# 8051.net
KiCad netlist of a schematic drawn in EAGLE
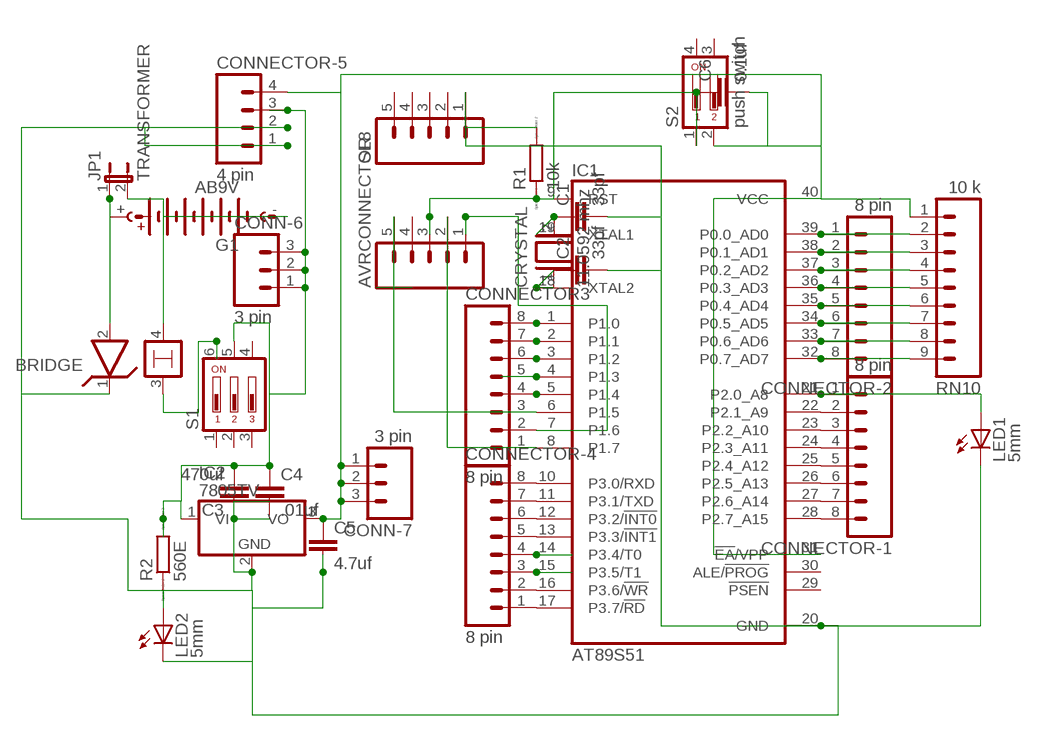
[diagram p0: schematic, sheet 1]

(export (version "E")
  (design (tool "Eeschema 10.0.6"))
  (components
    (comp (ref "AVRCONNECTOR")
      (value "M05")
      (footprint "eagle-import:05P")
      (libsource (lib "eagle-import") (part "M05"))
    )
    (comp (ref "BRIDGE")
      (value "LM399H")
      (footprint "eagle-import:TO39_4")
      (libsource (lib "eagle-import") (part "LM399H"))
    )
    (comp (ref "C1")
      (value "33pf")
      (footprint "eagle-import:C025-024X044")
      (libsource (lib "eagle-import") (part "C-EU025-024X044"))
    )
    (comp (ref "C2")
      (value "33pf")
      (footprint "eagle-import:C025-024X044")
      (libsource (lib "eagle-import") (part "C-EU025-024X044"))
    )
    (comp (ref "C3")
      (value "470uf")
      (footprint "eagle-import:C5B7.2")
      (libsource (lib "eagle-import") (part "C5/7.2"))
    )
    (comp (ref "C4")
      (value ".01uf")
      (footprint "eagle-import:C2.5-3")
      (libsource (lib "eagle-import") (part "C2,5-3"))
    )
    (comp (ref "C5")
      (value "4.7uf")
      (footprint "eagle-import:C2.5-3")
      (libsource (lib "eagle-import") (part "C2,5-3"))
    )
    (comp (ref "C6")
      (value "0.1uf")
      (footprint "eagle-import:C2.5-3")
      (libsource (lib "eagle-import") (part "C2,5-3"))
    )
    (comp (ref "CONN-6")
      (value "3 pin")
      (footprint "eagle-import:03P")
      (libsource (lib "eagle-import") (part "M03"))
    )
    (comp (ref "CONN-7")
      (value "3 pin")
      (footprint "eagle-import:03P")
      (libsource (lib "eagle-import") (part "M03"))
    )
    (comp (ref "CONNECTOR-1")
      (value "8 pin")
      (footprint "eagle-import:08P")
      (libsource (lib "eagle-import") (part "M08"))
    )
    (comp (ref "CONNECTOR-2")
      (value "8 pin")
      (footprint "eagle-import:08P")
      (libsource (lib "eagle-import") (part "M08"))
    )
    (comp (ref "CONNECTOR-4")
      (value "8 pin")
      (footprint "eagle-import:08P")
      (libsource (lib "eagle-import") (part "M08"))
    )
    (comp (ref "CONNECTOR-5")
      (value "4 pin")
      (footprint "eagle-import:04P")
      (libsource (lib "eagle-import") (part "M04"))
    )
    (comp (ref "CONNECTOR3")
      (value "8 pin")
      (footprint "eagle-import:08P")
      (libsource (lib "eagle-import") (part "M08"))
    )
    (comp (ref "CRYSTAL")
      (value "11.0592 mhz")
      (footprint "eagle-import:QS")
      (libsource (lib "eagle-import") (part "XTAL/S"))
    )
    (comp (ref "G1")
      (value "AB9V")
      (footprint "eagle-import:AB9V")
      (libsource (lib "eagle-import") (part "AB9V"))
    )
    (comp (ref "IC1")
      (value "AT89S51")
      (footprint "eagle-import:DIL40")
      (libsource (lib "eagle-import") (part "AT89C51-PC12"))
    )
    (comp (ref "IC2")
      (value "7805TV")
      (footprint "eagle-import:TO220V")
      (libsource (lib "eagle-import") (part "78TV05"))
    )
    (comp (ref "JP1")
      (value "TRANSFORMER")
      (footprint "eagle-import:JP1")
      (libsource (lib "eagle-import") (part "JP1E"))
    )
    (comp (ref "LED1")
      (value "5mm")
      (footprint "eagle-import:LED5MM")
      (libsource (lib "eagle-import") (part "LED5MM"))
    )
    (comp (ref "LED2")
      (value "5mm")
      (footprint "eagle-import:LED5MM")
      (libsource (lib "eagle-import") (part "LED5MM"))
    )
    (comp (ref "R1")
      (value "10k")
      (footprint "eagle-import:0204_7")
      (libsource (lib "eagle-import") (part "R0204/7"))
    )
    (comp (ref "R2")
      (value "560E")
      (footprint "eagle-import:0204_7")
      (libsource (lib "eagle-import") (part "R0204/7"))
    )
    (comp (ref "RN10")
      (value "10 k")
      (footprint "eagle-import:09P")
      (libsource (lib "eagle-import") (part "M09"))
    )
    (comp (ref "S1")
      (value "DA03")
      (footprint "eagle-import:DA-03")
      (fields (field (name "MPN") "MCDA03"))
      (libsource (lib "eagle-import") (part "DA03"))
    )
    (comp (ref "S2")
      (value "push switch")
      (footprint "eagle-import:DP-02")
      (fields (field (name "MPN") "MCDP02"))
      (libsource (lib "eagle-import") (part "DP02"))
    )
    (comp (ref "SL8")
      (value "M05")
      (footprint "eagle-import:05P")
      (libsource (lib "eagle-import") (part "M05"))
    )
  )
  (nets
    (net (code "1") (name "Net-(BRIDGE-Pad2)") (class "Default")
      (node (ref "BRIDGE") (pin "2") (pinfunction "2_2") (pintype "input"))
      (node (ref "G1") (pin "+") (pinfunction "+_+") (pintype "passive"))
      (node (ref "JP1") (pin "1") (pinfunction "1_1") (pintype "passive"))
    )
    (net (code "2") (name "Net-(BRIDGE-Pad3)") (class "Default")
      (node (ref "BRIDGE") (pin "3") (pinfunction "3_3") (pintype "input"))
      (node (ref "S1") (pin "6") (pinfunction "6_6") (pintype "passive"))
    )
    (net (code "3") (name "Net-(BRIDGE-Pad4)") (class "Default")
      (node (ref "BRIDGE") (pin "4") (pinfunction "4_4") (pintype "input"))
      (node (ref "G1") (pin "-") (pinfunction "-_-") (pintype "passive"))
      (node (ref "JP1") (pin "2") (pinfunction "2_2") (pintype "passive"))
    )
    (net (code "4") (name "Net-(IC1-GND)") (class "Default")
      (node (ref "BRIDGE") (pin "1") (pinfunction "1_1") (pintype "input"))
      (node (ref "C1") (pin "2") (pinfunction "2_2") (pintype "passive"))
      (node (ref "C2") (pin "2") (pinfunction "2_2") (pintype "passive"))
      (node (ref "C3") (pin "1") (pinfunction "1_1") (pintype "passive"))
      (node (ref "C4") (pin "2") (pinfunction "2_2") (pintype "passive"))
      (node (ref "C5") (pin "2") (pinfunction "2_2") (pintype "passive"))
      (node (ref "CONNECTOR-5") (pin "1") (pinfunction "1_1") (pintype "passive"))
      (node (ref "CONNECTOR-5") (pin "2") (pinfunction "2_2") (pintype "passive"))
      (node (ref "IC1") (pin "20") (pinfunction "GND_20") (pintype "power_in"))
      (node (ref "IC2") (pin "2") (pinfunction "GND_2") (pintype "passive"))
      (node (ref "LED1") (pin "K") (pinfunction "C_K") (pintype "passive"))
      (node (ref "LED2") (pin "K") (pinfunction "C_K") (pintype "passive"))
      (node (ref "R1") (pin "2") (pinfunction "2_2") (pintype "passive"))
      (node (ref "SL8") (pin "1") (pinfunction "1_1") (pintype "passive"))
    )
    (net (code "5") (name "Net-(IC1-P0.0_AD0)") (class "Default")
      (node (ref "CONNECTOR-2") (pin "1") (pinfunction "1_1") (pintype "passive"))
      (node (ref "IC1") (pin "39") (pinfunction "P0.0_AD0_39") (pintype "bidirectional"))
      (node (ref "RN10") (pin "2") (pinfunction "2_2") (pintype "passive"))
    )
    (net (code "6") (name "Net-(IC1-P0.1_AD1)") (class "Default")
      (node (ref "CONNECTOR-2") (pin "2") (pinfunction "2_2") (pintype "passive"))
      (node (ref "IC1") (pin "38") (pinfunction "P0.1_AD1_38") (pintype "bidirectional"))
      (node (ref "RN10") (pin "3") (pinfunction "3_3") (pintype "passive"))
    )
    (net (code "7") (name "Net-(IC1-P0.2_AD2)") (class "Default")
      (node (ref "CONNECTOR-2") (pin "3") (pinfunction "3_3") (pintype "passive"))
      (node (ref "IC1") (pin "37") (pinfunction "P0.2_AD2_37") (pintype "bidirectional"))
      (node (ref "RN10") (pin "4") (pinfunction "4_4") (pintype "passive"))
    )
    (net (code "8") (name "Net-(IC1-P0.3_AD3)") (class "Default")
      (node (ref "CONNECTOR-2") (pin "4") (pinfunction "4_4") (pintype "passive"))
      (node (ref "IC1") (pin "36") (pinfunction "P0.3_AD3_36") (pintype "bidirectional"))
      (node (ref "RN10") (pin "5") (pinfunction "5_5") (pintype "passive"))
    )
    (net (code "9") (name "Net-(IC1-P0.4_AD4)") (class "Default")
      (node (ref "CONNECTOR-2") (pin "5") (pinfunction "5_5") (pintype "passive"))
      (node (ref "IC1") (pin "35") (pinfunction "P0.4_AD4_35") (pintype "bidirectional"))
      (node (ref "RN10") (pin "6") (pinfunction "6_6") (pintype "passive"))
    )
    (net (code "10") (name "Net-(IC1-P0.5_AD5)") (class "Default")
      (node (ref "CONNECTOR-2") (pin "6") (pinfunction "6_6") (pintype "passive"))
      (node (ref "IC1") (pin "34") (pinfunction "P0.5_AD5_34") (pintype "bidirectional"))
      (node (ref "RN10") (pin "7") (pinfunction "7_7") (pintype "passive"))
    )
    (net (code "11") (name "Net-(IC1-P0.6_AD6)") (class "Default")
      (node (ref "CONNECTOR-2") (pin "7") (pinfunction "7_7") (pintype "passive"))
      (node (ref "IC1") (pin "33") (pinfunction "P0.6_AD6_33") (pintype "bidirectional"))
      (node (ref "RN10") (pin "8") (pinfunction "8_8") (pintype "passive"))
    )
    (net (code "12") (name "Net-(IC1-P0.7_AD7)") (class "Default")
      (node (ref "CONNECTOR-2") (pin "8") (pinfunction "8_8") (pintype "passive"))
      (node (ref "IC1") (pin "32") (pinfunction "P0.7_AD7_32") (pintype "bidirectional"))
      (node (ref "RN10") (pin "9") (pinfunction "9_9") (pintype "passive"))
    )
    (net (code "13") (name "Net-(IC1-P1.0)") (class "Default")
      (node (ref "CONNECTOR3") (pin "8") (pinfunction "8_8") (pintype "passive"))
      (node (ref "IC1") (pin "1") (pinfunction "P1.0_1") (pintype "bidirectional"))
    )
    (net (code "14") (name "Net-(IC1-P1.1)") (class "Default")
      (node (ref "CONNECTOR3") (pin "7") (pinfunction "7_7") (pintype "passive"))
      (node (ref "IC1") (pin "2") (pinfunction "P1.1_2") (pintype "bidirectional"))
    )
    (net (code "15") (name "Net-(IC1-P1.2)") (class "Default")
      (node (ref "CONNECTOR3") (pin "6") (pinfunction "6_6") (pintype "passive"))
      (node (ref "IC1") (pin "3") (pinfunction "P1.2_3") (pintype "bidirectional"))
    )
    (net (code "16") (name "Net-(IC1-P1.3)") (class "Default")
      (node (ref "CONNECTOR3") (pin "5") (pinfunction "5_5") (pintype "passive"))
      (node (ref "IC1") (pin "4") (pinfunction "P1.3_4") (pintype "bidirectional"))
    )
    (net (code "17") (name "Net-(IC1-P1.4)") (class "Default")
      (node (ref "CONNECTOR3") (pin "4") (pinfunction "4_4") (pintype "passive"))
      (node (ref "IC1") (pin "5") (pinfunction "P1.4_5") (pintype "bidirectional"))
    )
    (net (code "18") (name "Net-(IC1-P1.5)") (class "Default")
      (node (ref "AVRCONNECTOR") (pin "5") (pinfunction "5_5") (pintype "passive"))
      (node (ref "CONNECTOR3") (pin "3") (pinfunction "3_3") (pintype "passive"))
      (node (ref "IC1") (pin "6") (pinfunction "P1.5_6") (pintype "bidirectional"))
    )
    (net (code "19") (name "Net-(IC1-P1.6)") (class "Default")
      (node (ref "AVRCONNECTOR") (pin "1") (pinfunction "1_1") (pintype "passive"))
      (node (ref "CONNECTOR3") (pin "2") (pinfunction "2_2") (pintype "passive"))
      (node (ref "IC1") (pin "7") (pinfunction "P1.6_7") (pintype "bidirectional"))
    )
    (net (code "20") (name "Net-(IC1-P1.7)") (class "Default")
      (node (ref "AVRCONNECTOR") (pin "2") (pinfunction "2_2") (pintype "passive"))
      (node (ref "CONNECTOR3") (pin "1") (pinfunction "1_1") (pintype "passive"))
      (node (ref "IC1") (pin "8") (pinfunction "P1.7_8") (pintype "bidirectional"))
    )
    (net (code "21") (name "Net-(IC1-P2.0_A8)") (class "Default")
      (node (ref "CONNECTOR-1") (pin "1") (pinfunction "1_1") (pintype "passive"))
      (node (ref "IC1") (pin "21") (pinfunction "P2.0_A8_21") (pintype "bidirectional"))
      (node (ref "LED1") (pin "A") (pinfunction "A_A") (pintype "passive"))
    )
    (net (code "22") (name "Net-(IC1-P2.1_A9)") (class "Default")
      (node (ref "CONNECTOR-1") (pin "2") (pinfunction "2_2") (pintype "passive"))
      (node (ref "IC1") (pin "22") (pinfunction "P2.1_A9_22") (pintype "bidirectional"))
    )
    (net (code "23") (name "Net-(IC1-P2.2_A10)") (class "Default")
      (node (ref "CONNECTOR-1") (pin "3") (pinfunction "3_3") (pintype "passive"))
      (node (ref "IC1") (pin "23") (pinfunction "P2.2_A10_23") (pintype "bidirectional"))
    )
    (net (code "24") (name "Net-(IC1-P2.3_A11)") (class "Default")
      (node (ref "CONNECTOR-1") (pin "4") (pinfunction "4_4") (pintype "passive"))
      (node (ref "IC1") (pin "24") (pinfunction "P2.3_A11_24") (pintype "bidirectional"))
    )
    (net (code "25") (name "Net-(IC1-P2.4_A12)") (class "Default")
      (node (ref "CONNECTOR-1") (pin "5") (pinfunction "5_5") (pintype "passive"))
      (node (ref "IC1") (pin "25") (pinfunction "P2.4_A12_25") (pintype "bidirectional"))
    )
    (net (code "26") (name "Net-(IC1-P2.5_A13)") (class "Default")
      (node (ref "CONNECTOR-1") (pin "6") (pinfunction "6_6") (pintype "passive"))
      (node (ref "IC1") (pin "26") (pinfunction "P2.5_A13_26") (pintype "bidirectional"))
    )
    (net (code "27") (name "Net-(IC1-P2.6_A14)") (class "Default")
      (node (ref "CONNECTOR-1") (pin "7") (pinfunction "7_7") (pintype "passive"))
      (node (ref "IC1") (pin "27") (pinfunction "P2.6_A14_27") (pintype "bidirectional"))
    )
    (net (code "28") (name "Net-(IC1-P2.7_A15)") (class "Default")
      (node (ref "CONNECTOR-1") (pin "8") (pinfunction "8_8") (pintype "passive"))
      (node (ref "IC1") (pin "28") (pinfunction "P2.7_A15_28") (pintype "bidirectional"))
    )
    (net (code "29") (name "Net-(IC1-P3.0{slash}RXD)") (class "Default")
      (node (ref "CONNECTOR-4") (pin "8") (pinfunction "8_8") (pintype "passive"))
      (node (ref "IC1") (pin "10") (pinfunction "P3.0/RXD_10") (pintype "bidirectional"))
    )
    (net (code "30") (name "Net-(IC1-P3.1{slash}TXD)") (class "Default")
      (node (ref "CONNECTOR-4") (pin "7") (pinfunction "7_7") (pintype "passive"))
      (node (ref "IC1") (pin "11") (pinfunction "P3.1/TXD_11") (pintype "bidirectional"))
    )
    (net (code "31") (name "Net-(IC1-P3.2{slash}~{INT0})") (class "Default")
      (node (ref "CONNECTOR-4") (pin "6") (pinfunction "6_6") (pintype "passive"))
      (node (ref "IC1") (pin "12") (pinfunction "P3.2/~{INT0}_12") (pintype "bidirectional"))
    )
    (net (code "32") (name "Net-(IC1-P3.3{slash}~{INT1})") (class "Default")
      (node (ref "CONNECTOR-4") (pin "5") (pinfunction "5_5") (pintype "passive"))
      (node (ref "IC1") (pin "13") (pinfunction "P3.3/~{INT1}_13") (pintype "bidirectional"))
    )
    (net (code "33") (name "Net-(IC1-P3.4{slash}T0)") (class "Default")
      (node (ref "CONNECTOR-4") (pin "4") (pinfunction "4_4") (pintype "passive"))
      (node (ref "IC1") (pin "14") (pinfunction "P3.4/T0_14") (pintype "bidirectional"))
    )
    (net (code "34") (name "Net-(IC1-P3.5{slash}T1)") (class "Default")
      (node (ref "CONNECTOR-4") (pin "3") (pinfunction "3_3") (pintype "passive"))
      (node (ref "IC1") (pin "15") (pinfunction "P3.5/T1_15") (pintype "bidirectional"))
    )
    (net (code "35") (name "Net-(IC1-P3.6{slash}~{WR})") (class "Default")
      (node (ref "CONNECTOR-4") (pin "2") (pinfunction "2_2") (pintype "passive"))
      (node (ref "IC1") (pin "16") (pinfunction "P3.6/~{WR}_16") (pintype "bidirectional"))
    )
    (net (code "36") (name "Net-(IC1-P3.7{slash}~{RD})") (class "Default")
      (node (ref "CONNECTOR-4") (pin "1") (pinfunction "1_1") (pintype "passive"))
      (node (ref "IC1") (pin "17") (pinfunction "P3.7/~{RD}_17") (pintype "bidirectional"))
    )
    (net (code "37") (name "Net-(IC1-RST)") (class "Default")
      (node (ref "AVRCONNECTOR") (pin "3") (pinfunction "3_3") (pintype "passive"))
      (node (ref "C6") (pin "1") (pinfunction "1_1") (pintype "passive"))
      (node (ref "IC1") (pin "9") (pinfunction "RST_9") (pintype "input"))
      (node (ref "R1") (pin "1") (pinfunction "1_1") (pintype "passive"))
      (node (ref "S2") (pin "1") (pinfunction "1_1") (pintype "passive"))
    )
    (net (code "38") (name "Net-(IC1-VCC)") (class "Default")
      (node (ref "C5") (pin "1") (pinfunction "1_1") (pintype "passive"))
      (node (ref "C6") (pin "2") (pinfunction "2_2") (pintype "passive"))
      (node (ref "CONN-7") (pin "1") (pinfunction "1_1") (pintype "passive"))
      (node (ref "CONN-7") (pin "2") (pinfunction "2_2") (pintype "passive"))
      (node (ref "CONN-7") (pin "3") (pinfunction "3_3") (pintype "passive"))
      (node (ref "CONNECTOR-5") (pin "4") (pinfunction "4_4") (pintype "passive"))
      (node (ref "IC1") (pin "31") (pinfunction "~{EA}/VPP_31") (pintype "input"))
      (node (ref "IC1") (pin "40") (pinfunction "VCC_40") (pintype "power_in"))
      (node (ref "IC2") (pin "3") (pinfunction "VO_3") (pintype "passive"))
      (node (ref "RN10") (pin "1") (pinfunction "1_1") (pintype "passive"))
      (node (ref "S2") (pin "2") (pinfunction "2_2") (pintype "passive"))
    )
    (net (code "39") (name "Net-(IC1-XTAL1)") (class "Default")
      (node (ref "C1") (pin "1") (pinfunction "1_1") (pintype "passive"))
      (node (ref "CRYSTAL") (pin "2") (pinfunction "2_2") (pintype "passive"))
      (node (ref "IC1") (pin "19") (pinfunction "XTAL1_19") (pintype "input"))
    )
    (net (code "40") (name "Net-(IC1-XTAL2)") (class "Default")
      (node (ref "C2") (pin "1") (pinfunction "1_1") (pintype "passive"))
      (node (ref "CRYSTAL") (pin "1") (pinfunction "1_1") (pintype "passive"))
      (node (ref "IC1") (pin "18") (pinfunction "XTAL2_18") (pintype "input"))
    )
    (net (code "41") (name "Net-(IC2-VI)") (class "Default")
      (node (ref "C3") (pin "2") (pinfunction "2_2") (pintype "passive"))
      (node (ref "C4") (pin "1") (pinfunction "1_1") (pintype "passive"))
      (node (ref "CONN-6") (pin "1") (pinfunction "1_1") (pintype "passive"))
      (node (ref "CONN-6") (pin "2") (pinfunction "2_2") (pintype "passive"))
      (node (ref "CONN-6") (pin "3") (pinfunction "3_3") (pintype "passive"))
      (node (ref "CONNECTOR-5") (pin "3") (pinfunction "3_3") (pintype "passive"))
      (node (ref "IC2") (pin "1") (pinfunction "VI_1") (pintype "input"))
      (node (ref "R2") (pin "2") (pinfunction "2_2") (pintype "passive"))
      (node (ref "S1") (pin "5") (pinfunction "5_5") (pintype "passive"))
    )
    (net (code "42") (name "Net-(LED2-PadA)") (class "Default")
      (node (ref "LED2") (pin "A") (pinfunction "A_A") (pintype "passive"))
      (node (ref "R2") (pin "1") (pinfunction "1_1") (pintype "passive"))
    )
    (net (code "43") (name "unconnected-(AVRCONNECTOR-Pad4)") (class "Default")
      (node (ref "AVRCONNECTOR") (pin "4") (pinfunction "4_4") (pintype "passive"))
    )
    (net (code "44") (name "unconnected-(IC1-ALE{slash}~{PROG}-Pad30)") (class "Default")
      (node (ref "IC1") (pin "30") (pinfunction "ALE/~{PROG}_30") (pintype "output"))
    )
    (net (code "45") (name "unconnected-(IC1-~{PSEN}-Pad29)") (class "Default")
      (node (ref "IC1") (pin "29") (pinfunction "~{PSEN}_29") (pintype "output"))
    )
    (net (code "46") (name "unconnected-(S1-Pad1)") (class "Default")
      (node (ref "S1") (pin "1") (pinfunction "1_1") (pintype "passive"))
    )
    (net (code "47") (name "unconnected-(S1-Pad2)") (class "Default")
      (node (ref "S1") (pin "2") (pinfunction "2_2") (pintype "passive"))
    )
    (net (code "48") (name "unconnected-(S1-Pad3)") (class "Default")
      (node (ref "S1") (pin "3") (pinfunction "3_3") (pintype "passive"))
    )
    (net (code "49") (name "unconnected-(S1-Pad4)") (class "Default")
      (node (ref "S1") (pin "4") (pinfunction "4_4") (pintype "passive"))
    )
    (net (code "50") (name "unconnected-(S2-Pad3)") (class "Default")
      (node (ref "S2") (pin "3") (pinfunction "3_3") (pintype "passive"))
    )
    (net (code "51") (name "unconnected-(S2-Pad4)") (class "Default")
      (node (ref "S2") (pin "4") (pinfunction "4_4") (pintype "passive"))
    )
    (net (code "52") (name "unconnected-(SL8-Pad2)") (class "Default")
      (node (ref "SL8") (pin "2") (pinfunction "2_2") (pintype "passive"))
    )
    (net (code "53") (name "unconnected-(SL8-Pad3)") (class "Default")
      (node (ref "SL8") (pin "3") (pinfunction "3_3") (pintype "passive"))
    )
    (net (code "54") (name "unconnected-(SL8-Pad4)") (class "Default")
      (node (ref "SL8") (pin "4") (pinfunction "4_4") (pintype "passive"))
    )
    (net (code "55") (name "unconnected-(SL8-Pad5)") (class "Default")
      (node (ref "SL8") (pin "5") (pinfunction "5_5") (pintype "passive"))
    )
  )
)
